# XPanel.net
KiCad netlist of a schematic drawn in EAGLE
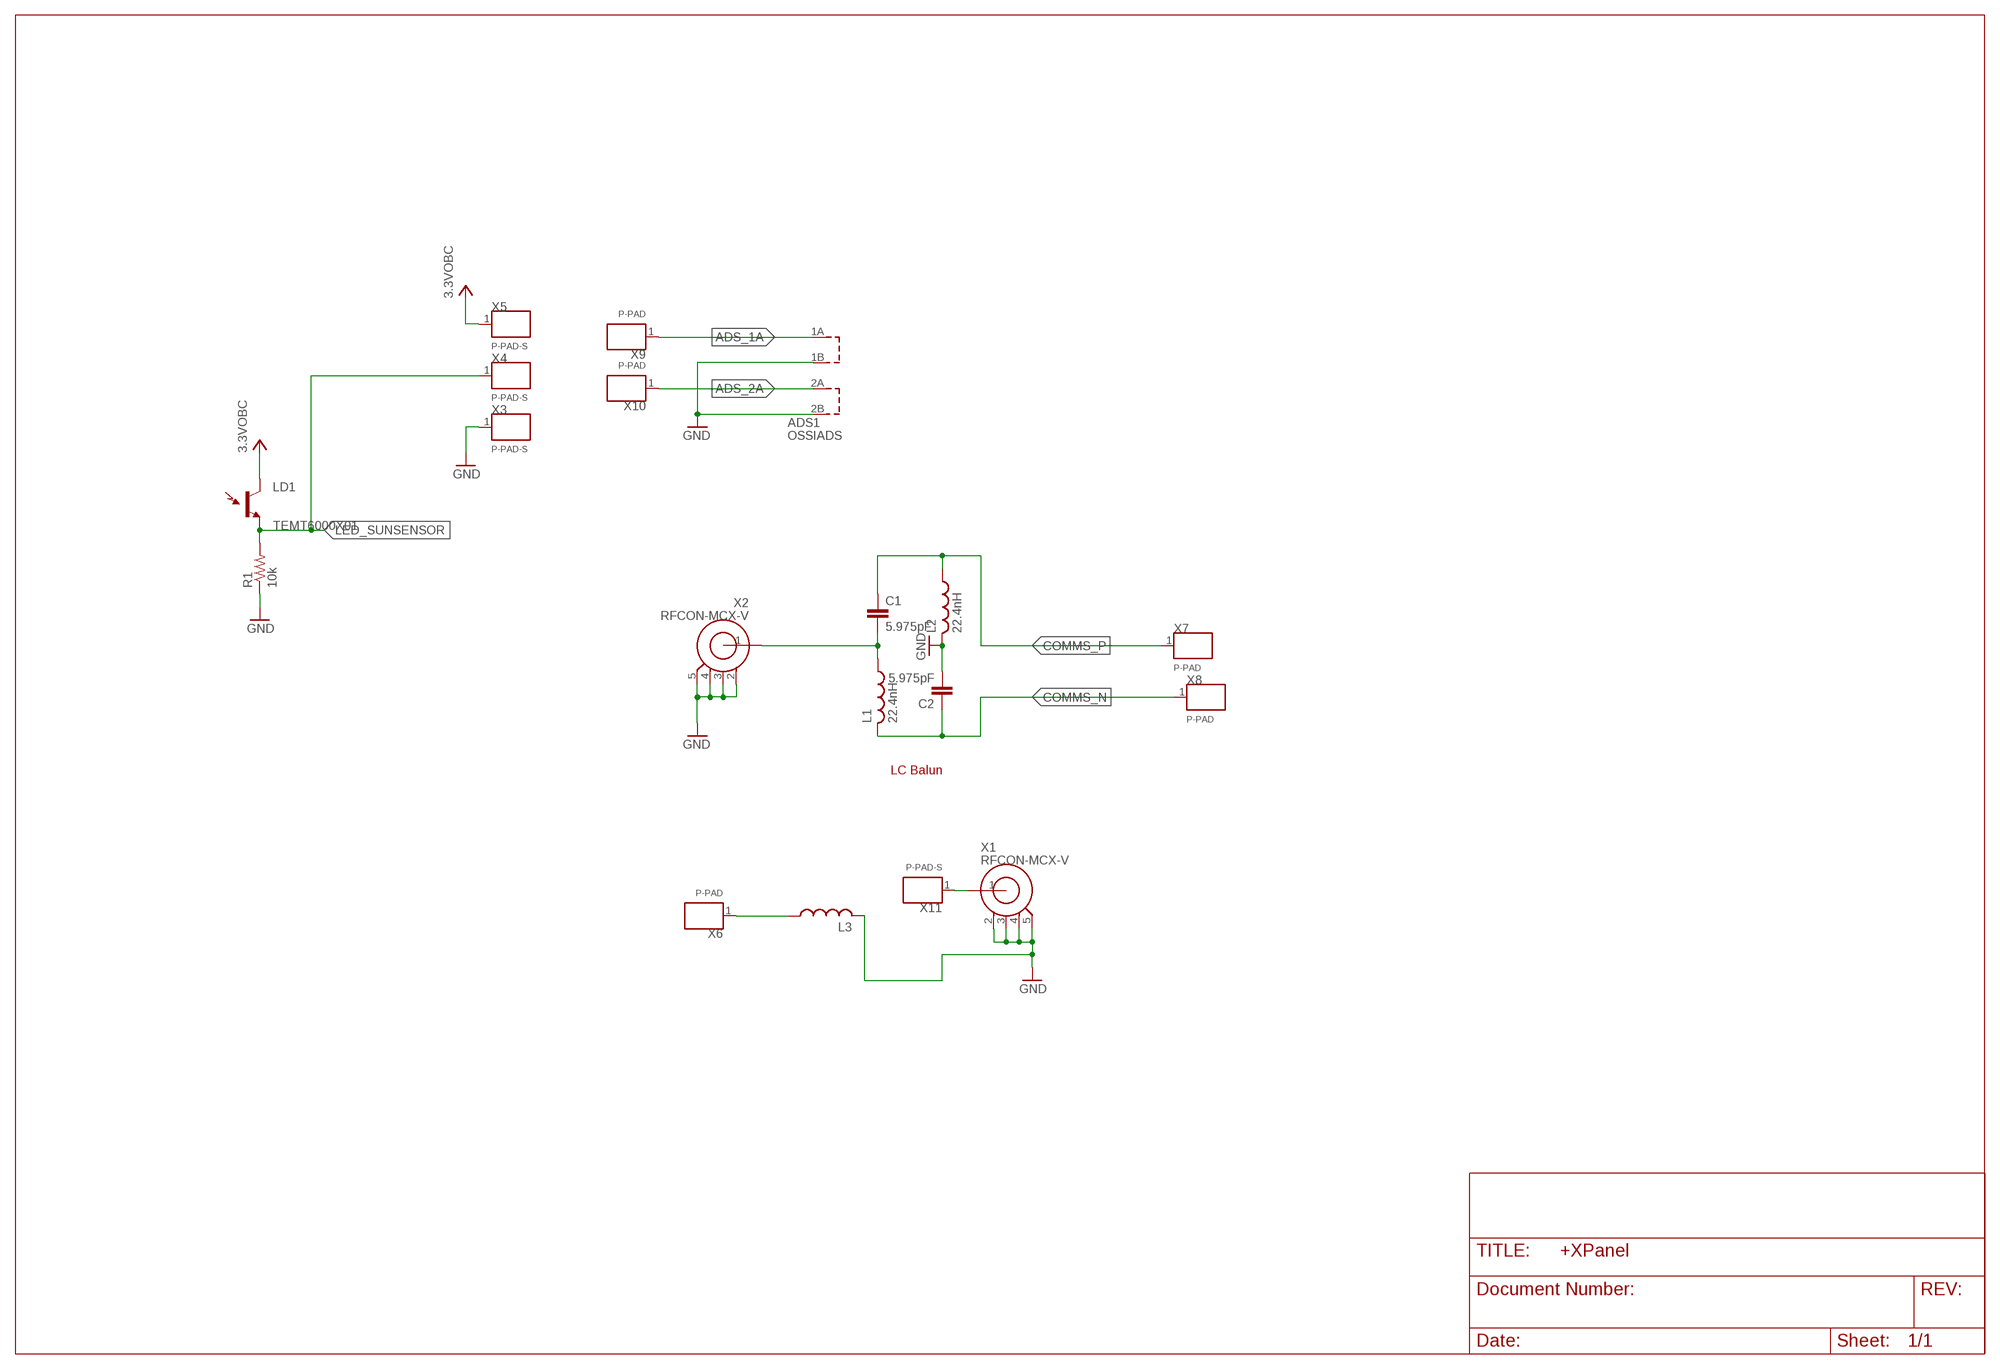
[diagram p0: schematic, sheet 1]

(export (version "E")
  (design (tool "Eeschema 10.0.6"))
  (components
    (comp (ref "ADS1")
      (value "OSSIADS")
      (footprint "eagle-import:OSSIADS")
      (libsource (lib "eagle-import") (part "OSSIADS"))
    )
    (comp (ref "C1")
      (value "5.975pF")
      (footprint "eagle-import:C0805(2012)")
      (libsource (lib "eagle-import") (part "C0805(2012)"))
    )
    (comp (ref "C2")
      (value "5.975pF")
      (footprint "eagle-import:C0805(2012)")
      (libsource (lib "eagle-import") (part "C0805(2012)"))
    )
    (comp (ref "L1")
      (value "22.4nH")
      (footprint "eagle-import:L0805(2012)")
      (libsource (lib "eagle-import") (part "L0805(2012)"))
    )
    (comp (ref "L2")
      (value "22.4nH")
      (footprint "eagle-import:L0805(2012)")
      (libsource (lib "eagle-import") (part "L0805(2012)"))
    )
    (comp (ref "L3")
      (value "L-US0207/10")
      (footprint "eagle-import:0207_10")
      (libsource (lib "eagle-import") (part "L-US0207/10"))
    )
    (comp (ref "LD1")
      (value "TEMT6000X01")
      (footprint "eagle-import:TEMT6000-SEN")
      (libsource (lib "eagle-import") (part "TEMT6000X01"))
    )
    (comp (ref "R1")
      (value "10k")
      (footprint "eagle-import:R0805(2012)")
      (libsource (lib "eagle-import") (part "R0805(2012)"))
    )
    (comp (ref "X1")
      (value "RFCON-MCX-V")
      (footprint "eagle-import:MCX-V")
      (libsource (lib "eagle-import") (part "RFCON-MCX-V"))
    )
    (comp (ref "X2")
      (value "RFCON-MCX-V")
      (footprint "eagle-import:MCX-V")
      (libsource (lib "eagle-import") (part "RFCON-MCX-V"))
    )
    (comp (ref "X3")
      (value "P-PAD-S")
      (footprint "eagle-import:P-PAD-S")
      (libsource (lib "eagle-import") (part "P-PAD-S"))
    )
    (comp (ref "X4")
      (value "P-PAD-S")
      (footprint "eagle-import:P-PAD-S")
      (libsource (lib "eagle-import") (part "P-PAD-S"))
    )
    (comp (ref "X5")
      (value "P-PAD-S")
      (footprint "eagle-import:P-PAD-S")
      (libsource (lib "eagle-import") (part "P-PAD-S"))
    )
    (comp (ref "X6")
      (value "P-PAD")
      (footprint "eagle-import:P-PAD")
      (libsource (lib "eagle-import") (part "P-PAD"))
    )
    (comp (ref "X7")
      (value "P-PAD")
      (footprint "eagle-import:P-PAD")
      (libsource (lib "eagle-import") (part "P-PAD"))
    )
    (comp (ref "X8")
      (value "P-PAD")
      (footprint "eagle-import:P-PAD")
      (libsource (lib "eagle-import") (part "P-PAD"))
    )
    (comp (ref "X9")
      (value "P-PAD")
      (footprint "eagle-import:P-PAD")
      (libsource (lib "eagle-import") (part "P-PAD"))
    )
    (comp (ref "X10")
      (value "P-PAD")
      (footprint "eagle-import:P-PAD")
      (libsource (lib "eagle-import") (part "P-PAD"))
    )
    (comp (ref "X11")
      (value "P-PAD-S")
      (footprint "eagle-import:P-PAD-S")
      (libsource (lib "eagle-import") (part "P-PAD-S"))
    )
  )
  (nets
    (net (code "1") (name "3.3VOBC") (class "Default")
      (node (ref "LD1") (pin "COLLECTOR") (pinfunction "C1_COLLECTOR") (pintype "passive"))
      (node (ref "X5") (pin "1") (pinfunction "P$1_1") (pintype "bidirectional"))
    )
    (net (code "2") (name "ADS_1A") (class "Default")
      (node (ref "ADS1") (pin "1A") (pinfunction "1A_1A") (pintype "passive"))
      (node (ref "X9") (pin "1") (pinfunction "P$1_1") (pintype "bidirectional"))
    )
    (net (code "3") (name "ADS_2A") (class "Default")
      (node (ref "ADS1") (pin "2A") (pinfunction "2A_2A") (pintype "passive"))
      (node (ref "X10") (pin "1") (pinfunction "P$1_1") (pintype "bidirectional"))
    )
    (net (code "4") (name "COMMS_N") (class "Default")
      (node (ref "C2") (pin "1") (pinfunction "1_1") (pintype "passive"))
      (node (ref "L1") (pin "2") (pinfunction "2_2") (pintype "passive"))
      (node (ref "X8") (pin "1") (pinfunction "P$1_1") (pintype "bidirectional"))
    )
    (net (code "5") (name "COMMS_P") (class "Default")
      (node (ref "C1") (pin "1") (pinfunction "1_1") (pintype "passive"))
      (node (ref "L2") (pin "1") (pinfunction "1_1") (pintype "passive"))
      (node (ref "X7") (pin "1") (pinfunction "P$1_1") (pintype "bidirectional"))
    )
    (net (code "6") (name "GND") (class "Default")
      (node (ref "ADS1") (pin "1B") (pinfunction "1B_1B") (pintype "passive"))
      (node (ref "ADS1") (pin "2B") (pinfunction "2B_2B") (pintype "passive"))
      (node (ref "C2") (pin "2") (pinfunction "2_2") (pintype "passive"))
      (node (ref "L2") (pin "2") (pinfunction "2_2") (pintype "passive"))
      (node (ref "L3") (pin "2") (pinfunction "2_2") (pintype "passive"))
      (node (ref "R1") (pin "1") (pinfunction "1_1") (pintype "passive"))
      (node (ref "X1") (pin "2") (pinfunction "2_2") (pintype "power_in"))
      (node (ref "X1") (pin "3") (pinfunction "3_3") (pintype "power_in"))
      (node (ref "X1") (pin "4") (pinfunction "4_4") (pintype "power_in"))
      (node (ref "X1") (pin "5") (pinfunction "5_5") (pintype "power_in"))
      (node (ref "X2") (pin "2") (pinfunction "2_2") (pintype "power_in"))
      (node (ref "X2") (pin "3") (pinfunction "3_3") (pintype "power_in"))
      (node (ref "X2") (pin "4") (pinfunction "4_4") (pintype "power_in"))
      (node (ref "X2") (pin "5") (pinfunction "5_5") (pintype "power_in"))
      (node (ref "X3") (pin "1") (pinfunction "P$1_1") (pintype "bidirectional"))
    )
    (net (code "7") (name "LED_SUNSENSOR") (class "Default")
      (node (ref "LD1") (pin "EMITTER") (pinfunction "E1_EMITTER") (pintype "passive"))
      (node (ref "R1") (pin "2") (pinfunction "2_2") (pintype "passive"))
      (node (ref "X4") (pin "1") (pinfunction "P$1_1") (pintype "bidirectional"))
    )
    (net (code "8") (name "Net-(C1-Pad2)") (class "Default")
      (node (ref "C1") (pin "2") (pinfunction "2_2") (pintype "passive"))
      (node (ref "L1") (pin "1") (pinfunction "1_1") (pintype "passive"))
      (node (ref "X2") (pin "1") (pinfunction "1_1") (pintype "bidirectional"))
    )
    (net (code "9") (name "Net-(X6-P$1)") (class "Default")
      (node (ref "L3") (pin "1") (pinfunction "1_1") (pintype "passive"))
      (node (ref "X6") (pin "1") (pinfunction "P$1_1") (pintype "bidirectional"))
    )
    (net (code "10") (name "Net-(X11-P$1)") (class "Default")
      (node (ref "X1") (pin "1") (pinfunction "1_1") (pintype "bidirectional"))
      (node (ref "X11") (pin "1") (pinfunction "P$1_1") (pintype "bidirectional"))
    )
  )
)
